# RS485_Extension_Board.net
KiCad netlist of a schematic drawn in EAGLE
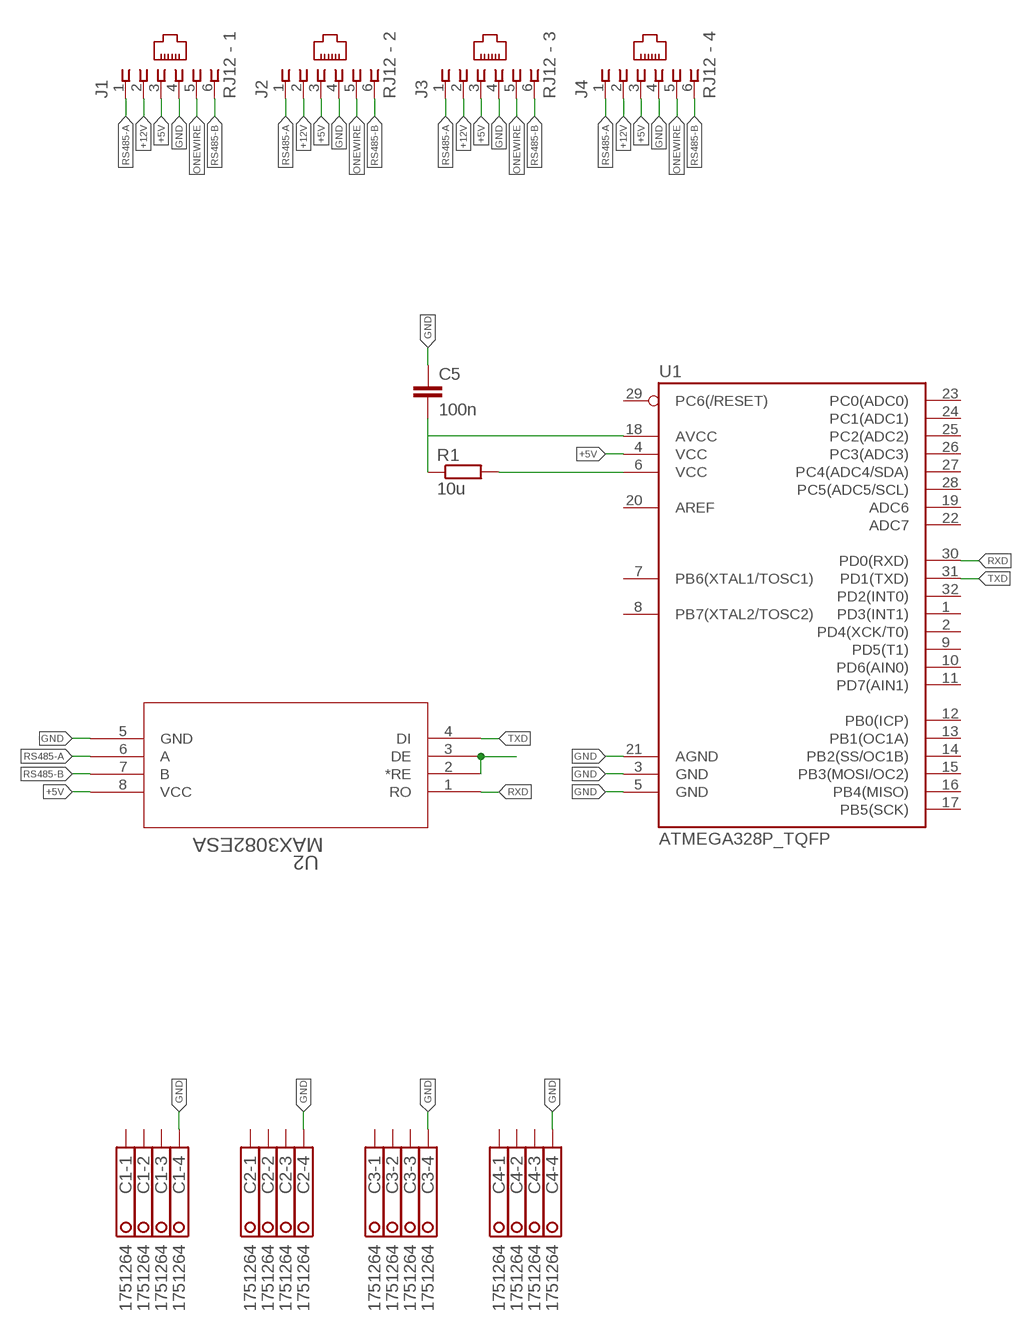
[diagram p0: schematic, sheet 1]

(export (version "E")
  (design (tool "Eeschema 10.0.6"))
  (components
    (comp (ref "C1")
      (value "1751264")
      (footprint "eagle-import:1751264")
      (libsource (lib "eagle-import") (part "1751264"))
    )
    (comp (ref "C2")
      (value "1751264")
      (footprint "eagle-import:1751264")
      (libsource (lib "eagle-import") (part "1751264"))
    )
    (comp (ref "C3")
      (value "1751264")
      (footprint "eagle-import:1751264")
      (libsource (lib "eagle-import") (part "1751264"))
    )
    (comp (ref "C4")
      (value "1751264")
      (footprint "eagle-import:1751264")
      (libsource (lib "eagle-import") (part "1751264"))
    )
    (comp (ref "C5")
      (value "100n")
      (footprint "eagle-import:C0805")
      (libsource (lib "eagle-import") (part "C-EUC0805"))
    )
    (comp (ref "J1")
      (value "RJ12 - 1")
      (footprint "eagle-import:520250-3")
      (libsource (lib "eagle-import") (part "520250-3"))
    )
    (comp (ref "J2")
      (value "RJ12 - 2")
      (footprint "eagle-import:520250-3")
      (libsource (lib "eagle-import") (part "520250-3"))
    )
    (comp (ref "J3")
      (value "RJ12 - 3")
      (footprint "eagle-import:520250-3")
      (libsource (lib "eagle-import") (part "520250-3"))
    )
    (comp (ref "J4")
      (value "RJ12 - 4")
      (footprint "eagle-import:520250-3")
      (libsource (lib "eagle-import") (part "520250-3"))
    )
    (comp (ref "R1")
      (value "10u")
      (footprint "eagle-import:M0805")
      (libsource (lib "eagle-import") (part "R-EU_M0805"))
    )
    (comp (ref "U1")
      (value "ATMEGA328P_TQFP")
      (footprint "eagle-import:TQFP32-08")
      (libsource (lib "eagle-import") (part "ATMEGA328P_TQFP"))
    )
    (comp (ref "U2")
      (value "MAX3082ESA")
      (footprint "eagle-import:21-0041B_8")
      (libsource (lib "eagle-import") (part "MAX3082ESA"))
    )
  )
  (nets
    (net (code "1") (name "+5V") (class "Default")
      (node (ref "C5") (pin "2") (pinfunction "2_2") (pintype "passive"))
      (node (ref "J1") (pin "3") (pinfunction "3_3") (pintype "passive"))
      (node (ref "J2") (pin "3") (pinfunction "3_3") (pintype "passive"))
      (node (ref "J3") (pin "3") (pinfunction "3_3") (pintype "passive"))
      (node (ref "J4") (pin "3") (pinfunction "3_3") (pintype "passive"))
      (node (ref "R1") (pin "1") (pinfunction "1_1") (pintype "passive"))
      (node (ref "U1") (pin "18") (pinfunction "AVCC_18") (pintype "bidirectional"))
      (node (ref "U1") (pin "4") (pinfunction "VCC_4") (pintype "bidirectional"))
      (node (ref "U2") (pin "8") (pinfunction "VCC_8") (pintype "power_in"))
    )
    (net (code "2") (name "+12V") (class "Default")
      (node (ref "J1") (pin "2") (pinfunction "2_2") (pintype "passive"))
      (node (ref "J2") (pin "2") (pinfunction "2_2") (pintype "passive"))
      (node (ref "J3") (pin "2") (pinfunction "2_2") (pintype "passive"))
      (node (ref "J4") (pin "2") (pinfunction "2_2") (pintype "passive"))
    )
    (net (code "3") (name "GND") (class "Default")
      (node (ref "C1") (pin "4") (pinfunction "K_4") (pintype "passive"))
      (node (ref "C2") (pin "4") (pinfunction "K_4") (pintype "passive"))
      (node (ref "C3") (pin "4") (pinfunction "K_4") (pintype "passive"))
      (node (ref "C4") (pin "4") (pinfunction "K_4") (pintype "passive"))
      (node (ref "C5") (pin "1") (pinfunction "1_1") (pintype "passive"))
      (node (ref "J1") (pin "4") (pinfunction "4_4") (pintype "passive"))
      (node (ref "J2") (pin "4") (pinfunction "4_4") (pintype "passive"))
      (node (ref "J3") (pin "4") (pinfunction "4_4") (pintype "passive"))
      (node (ref "J4") (pin "4") (pinfunction "4_4") (pintype "passive"))
      (node (ref "U1") (pin "21") (pinfunction "AGND_21") (pintype "bidirectional"))
      (node (ref "U1") (pin "3") (pinfunction "GND_3") (pintype "bidirectional"))
      (node (ref "U1") (pin "5") (pinfunction "GND_5") (pintype "bidirectional"))
      (node (ref "U2") (pin "5") (pinfunction "GND_5") (pintype "power_in"))
    )
    (net (code "4") (name "Net-(R1-Pad2)") (class "Default")
      (node (ref "R1") (pin "2") (pinfunction "2_2") (pintype "passive"))
      (node (ref "U1") (pin "6") (pinfunction "VCC_6") (pintype "bidirectional"))
    )
    (net (code "5") (name "Net-(U2-*RE)") (class "Default")
      (node (ref "U2") (pin "2") (pinfunction "*RE_2") (pintype "passive"))
      (node (ref "U2") (pin "3") (pinfunction "DE_3") (pintype "passive"))
    )
    (net (code "6") (name "ONEWIRE") (class "Default")
      (node (ref "J1") (pin "5") (pinfunction "5_5") (pintype "passive"))
      (node (ref "J2") (pin "5") (pinfunction "5_5") (pintype "passive"))
      (node (ref "J3") (pin "5") (pinfunction "5_5") (pintype "passive"))
      (node (ref "J4") (pin "5") (pinfunction "5_5") (pintype "passive"))
    )
    (net (code "7") (name "RS485-A") (class "Default")
      (node (ref "J1") (pin "1") (pinfunction "1_1") (pintype "passive"))
      (node (ref "J2") (pin "1") (pinfunction "1_1") (pintype "passive"))
      (node (ref "J3") (pin "1") (pinfunction "1_1") (pintype "passive"))
      (node (ref "J4") (pin "1") (pinfunction "1_1") (pintype "passive"))
      (node (ref "U2") (pin "6") (pinfunction "A_6") (pintype "passive"))
    )
    (net (code "8") (name "RS485-B") (class "Default")
      (node (ref "J1") (pin "6") (pinfunction "6_6") (pintype "passive"))
      (node (ref "J2") (pin "6") (pinfunction "6_6") (pintype "passive"))
      (node (ref "J3") (pin "6") (pinfunction "6_6") (pintype "passive"))
      (node (ref "J4") (pin "6") (pinfunction "6_6") (pintype "passive"))
      (node (ref "U2") (pin "7") (pinfunction "B_7") (pintype "passive"))
    )
    (net (code "9") (name "RXD") (class "Default")
      (node (ref "U1") (pin "30") (pinfunction "PD0(RXD)_30") (pintype "bidirectional"))
      (node (ref "U2") (pin "1") (pinfunction "RO_1") (pintype "passive"))
    )
    (net (code "10") (name "TXD") (class "Default")
      (node (ref "U1") (pin "31") (pinfunction "PD1(TXD)_31") (pintype "bidirectional"))
      (node (ref "U2") (pin "4") (pinfunction "DI_4") (pintype "passive"))
    )
    (net (code "11") (name "unconnected-(C1A-K-Pad1)") (class "Default")
      (node (ref "C1") (pin "1") (pinfunction "K_1") (pintype "passive"))
    )
    (net (code "12") (name "unconnected-(C1B-K-Pad2)") (class "Default")
      (node (ref "C1") (pin "2") (pinfunction "K_2") (pintype "passive"))
    )
    (net (code "13") (name "unconnected-(C1C-K-Pad3)") (class "Default")
      (node (ref "C1") (pin "3") (pinfunction "K_3") (pintype "passive"))
    )
    (net (code "14") (name "unconnected-(C2A-K-Pad1)") (class "Default")
      (node (ref "C2") (pin "1") (pinfunction "K_1") (pintype "passive"))
    )
    (net (code "15") (name "unconnected-(C2B-K-Pad2)") (class "Default")
      (node (ref "C2") (pin "2") (pinfunction "K_2") (pintype "passive"))
    )
    (net (code "16") (name "unconnected-(C2C-K-Pad3)") (class "Default")
      (node (ref "C2") (pin "3") (pinfunction "K_3") (pintype "passive"))
    )
    (net (code "17") (name "unconnected-(C3A-K-Pad1)") (class "Default")
      (node (ref "C3") (pin "1") (pinfunction "K_1") (pintype "passive"))
    )
    (net (code "18") (name "unconnected-(C3B-K-Pad2)") (class "Default")
      (node (ref "C3") (pin "2") (pinfunction "K_2") (pintype "passive"))
    )
    (net (code "19") (name "unconnected-(C3C-K-Pad3)") (class "Default")
      (node (ref "C3") (pin "3") (pinfunction "K_3") (pintype "passive"))
    )
    (net (code "20") (name "unconnected-(C4A-K-Pad1)") (class "Default")
      (node (ref "C4") (pin "1") (pinfunction "K_1") (pintype "passive"))
    )
    (net (code "21") (name "unconnected-(C4B-K-Pad2)") (class "Default")
      (node (ref "C4") (pin "2") (pinfunction "K_2") (pintype "passive"))
    )
    (net (code "22") (name "unconnected-(C4C-K-Pad3)") (class "Default")
      (node (ref "C4") (pin "3") (pinfunction "K_3") (pintype "passive"))
    )
    (net (code "23") (name "unconnected-(U1-ADC6-Pad19)") (class "Default")
      (node (ref "U1") (pin "19") (pinfunction "ADC6_19") (pintype "bidirectional"))
    )
    (net (code "24") (name "unconnected-(U1-ADC7-Pad22)") (class "Default")
      (node (ref "U1") (pin "22") (pinfunction "ADC7_22") (pintype "bidirectional"))
    )
    (net (code "25") (name "unconnected-(U1-AREF-Pad20)") (class "Default")
      (node (ref "U1") (pin "20") (pinfunction "AREF_20") (pintype "bidirectional"))
    )
    (net (code "26") (name "unconnected-(U1-PB0(ICP)-Pad12)") (class "Default")
      (node (ref "U1") (pin "12") (pinfunction "PB0(ICP)_12") (pintype "bidirectional"))
    )
    (net (code "27") (name "unconnected-(U1-PB1(OC1A)-Pad13)") (class "Default")
      (node (ref "U1") (pin "13") (pinfunction "PB1(OC1A)_13") (pintype "bidirectional"))
    )
    (net (code "28") (name "unconnected-(U1-PB2(SS{slash}OC1B)-Pad14)") (class "Default")
      (node (ref "U1") (pin "14") (pinfunction "PB2(SS/OC1B)_14") (pintype "bidirectional"))
    )
    (net (code "29") (name "unconnected-(U1-PB3(MOSI{slash}OC2)-Pad15)") (class "Default")
      (node (ref "U1") (pin "15") (pinfunction "PB3(MOSI/OC2)_15") (pintype "bidirectional"))
    )
    (net (code "30") (name "unconnected-(U1-PB4(MISO)-Pad16)") (class "Default")
      (node (ref "U1") (pin "16") (pinfunction "PB4(MISO)_16") (pintype "bidirectional"))
    )
    (net (code "31") (name "unconnected-(U1-PB5(SCK)-Pad17)") (class "Default")
      (node (ref "U1") (pin "17") (pinfunction "PB5(SCK)_17") (pintype "bidirectional"))
    )
    (net (code "32") (name "unconnected-(U1-PB6(XTAL1{slash}TOSC1)-Pad7)") (class "Default")
      (node (ref "U1") (pin "7") (pinfunction "PB6(XTAL1/TOSC1)_7") (pintype "bidirectional"))
    )
    (net (code "33") (name "unconnected-(U1-PB7(XTAL2{slash}TOSC2)-Pad8)") (class "Default")
      (node (ref "U1") (pin "8") (pinfunction "PB7(XTAL2/TOSC2)_8") (pintype "bidirectional"))
    )
    (net (code "34") (name "unconnected-(U1-PC0(ADC0)-Pad23)") (class "Default")
      (node (ref "U1") (pin "23") (pinfunction "PC0(ADC0)_23") (pintype "bidirectional"))
    )
    (net (code "35") (name "unconnected-(U1-PC1(ADC1)-Pad24)") (class "Default")
      (node (ref "U1") (pin "24") (pinfunction "PC1(ADC1)_24") (pintype "bidirectional"))
    )
    (net (code "36") (name "unconnected-(U1-PC2(ADC2)-Pad25)") (class "Default")
      (node (ref "U1") (pin "25") (pinfunction "PC2(ADC2)_25") (pintype "bidirectional"))
    )
    (net (code "37") (name "unconnected-(U1-PC3(ADC3)-Pad26)") (class "Default")
      (node (ref "U1") (pin "26") (pinfunction "PC3(ADC3)_26") (pintype "bidirectional"))
    )
    (net (code "38") (name "unconnected-(U1-PC4(ADC4{slash}SDA)-Pad27)") (class "Default")
      (node (ref "U1") (pin "27") (pinfunction "PC4(ADC4/SDA)_27") (pintype "bidirectional"))
    )
    (net (code "39") (name "unconnected-(U1-PC5(ADC5{slash}SCL)-Pad28)") (class "Default")
      (node (ref "U1") (pin "28") (pinfunction "PC5(ADC5/SCL)_28") (pintype "bidirectional"))
    )
    (net (code "40") (name "unconnected-(U1-PC6({slash}RESET)-Pad29)") (class "Default")
      (node (ref "U1") (pin "29") (pinfunction "PC6(/RESET)_29") (pintype "bidirectional"))
    )
    (net (code "41") (name "unconnected-(U1-PD2(INT0)-Pad32)") (class "Default")
      (node (ref "U1") (pin "32") (pinfunction "PD2(INT0)_32") (pintype "bidirectional"))
    )
    (net (code "42") (name "unconnected-(U1-PD3(INT1)-Pad1)") (class "Default")
      (node (ref "U1") (pin "1") (pinfunction "PD3(INT1)_1") (pintype "bidirectional"))
    )
    (net (code "43") (name "unconnected-(U1-PD4(XCK{slash}T0)-Pad2)") (class "Default")
      (node (ref "U1") (pin "2") (pinfunction "PD4(XCK/T0)_2") (pintype "bidirectional"))
    )
    (net (code "44") (name "unconnected-(U1-PD5(T1)-Pad9)") (class "Default")
      (node (ref "U1") (pin "9") (pinfunction "PD5(T1)_9") (pintype "bidirectional"))
    )
    (net (code "45") (name "unconnected-(U1-PD6(AIN0)-Pad10)") (class "Default")
      (node (ref "U1") (pin "10") (pinfunction "PD6(AIN0)_10") (pintype "bidirectional"))
    )
    (net (code "46") (name "unconnected-(U1-PD7(AIN1)-Pad11)") (class "Default")
      (node (ref "U1") (pin "11") (pinfunction "PD7(AIN1)_11") (pintype "bidirectional"))
    )
  )
)
